# Adafruit_DRV2605L.net
KiCad netlist of a schematic drawn in EAGLE
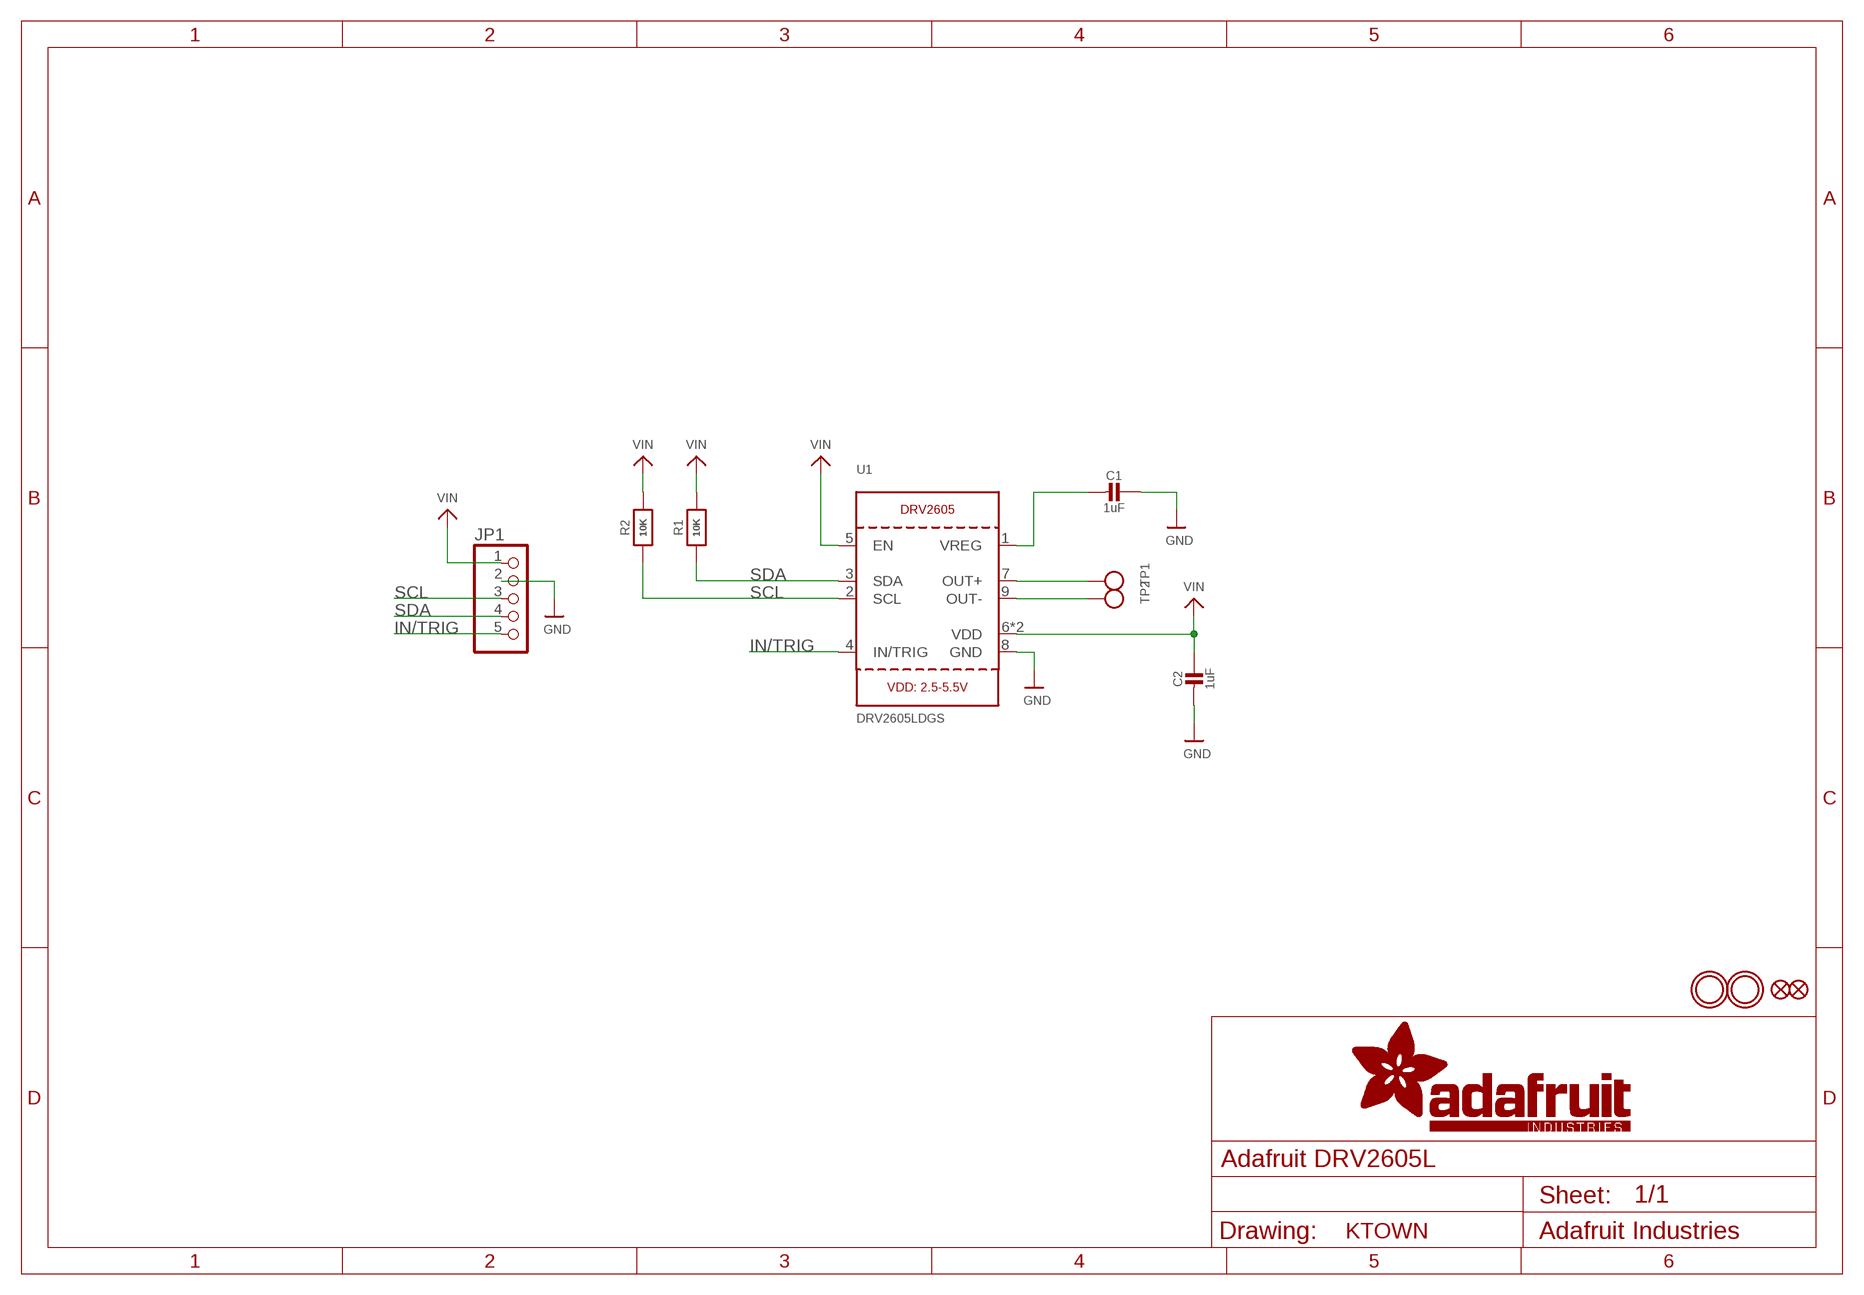
[diagram p0: schematic, sheet 1]

(export (version "E")
  (design (tool "Eeschema 10.0.6"))
  (components
    (comp (ref "C1")
      (value "1uF")
      (footprint "eagle-import:0805-NO")
      (libsource (lib "eagle-import") (part "CAP_CERAMIC0805-NOOUTLINE"))
    )
    (comp (ref "C2")
      (value "1uF")
      (footprint "eagle-import:0805-NO")
      (libsource (lib "eagle-import") (part "CAP_CERAMIC0805-NOOUTLINE"))
    )
    (comp (ref "FID1")
      (value "FIDUCIAL\"\"")
      (footprint "eagle-import:FIDUCIAL_1MM")
      (libsource (lib "eagle-import") (part "FIDUCIAL{dblquote}{dblquote}"))
    )
    (comp (ref "FID2")
      (value "FIDUCIAL\"\"")
      (footprint "eagle-import:FIDUCIAL_1MM")
      (libsource (lib "eagle-import") (part "FIDUCIAL{dblquote}{dblquote}"))
    )
    (comp (ref "JP1")
      (value "HEADER-1X576MIL_FULL")
      (footprint "eagle-import:1X05_ROUND_FULL_76")
      (libsource (lib "eagle-import") (part "HEADER-1X576MIL_FULL"))
    )
    (comp (ref "R1")
      (value "10K")
      (footprint "eagle-import:0805-NO")
      (libsource (lib "eagle-import") (part "RESISTOR0805_NOOUTLINE"))
    )
    (comp (ref "R2")
      (value "10K")
      (footprint "eagle-import:0805-NO")
      (libsource (lib "eagle-import") (part "RESISTOR0805_NOOUTLINE"))
    )
    (comp (ref "TP1")
      (value "TESTPOINTPAD2MM")
      (footprint "eagle-import:TESTPOINT_PAD_2MM")
      (libsource (lib "eagle-import") (part "TESTPOINTPAD2MM"))
    )
    (comp (ref "TP2")
      (value "TESTPOINTPAD2MM")
      (footprint "eagle-import:TESTPOINT_PAD_2MM")
      (libsource (lib "eagle-import") (part "TESTPOINTPAD2MM"))
    )
    (comp (ref "U$2")
      (value "MOUNTINGHOLE2.5")
      (footprint "eagle-import:MOUNTINGHOLE_2.5_PLATED")
      (libsource (lib "eagle-import") (part "MOUNTINGHOLE2.5"))
    )
    (comp (ref "U$3")
      (value "MOUNTINGHOLE2.5")
      (footprint "eagle-import:MOUNTINGHOLE_2.5_PLATED")
      (libsource (lib "eagle-import") (part "MOUNTINGHOLE2.5"))
    )
    (comp (ref "U1")
      (value "DRV2605LDGS")
      (footprint "eagle-import:PSOP10")
      (libsource (lib "eagle-import") (part "DRV2605_SOP"))
    )
  )
  (nets
    (net (code "1") (name "/IN{slash}TRIG") (class "Default")
      (node (ref "JP1") (pin "5") (pinfunction "5_5") (pintype "passive"))
      (node (ref "U1") (pin "4") (pinfunction "IN/TRIG_4") (pintype "input"))
    )
    (net (code "2") (name "/SCL") (class "Default")
      (node (ref "JP1") (pin "3") (pinfunction "3_3") (pintype "passive"))
      (node (ref "R2") (pin "1") (pinfunction "1_1") (pintype "passive"))
      (node (ref "U1") (pin "2") (pinfunction "SCL_2") (pintype "input"))
    )
    (net (code "3") (name "/SDA") (class "Default")
      (node (ref "JP1") (pin "4") (pinfunction "4_4") (pintype "passive"))
      (node (ref "R1") (pin "1") (pinfunction "1_1") (pintype "passive"))
      (node (ref "U1") (pin "3") (pinfunction "SDA_3") (pintype "bidirectional"))
    )
    (net (code "4") (name "GND") (class "Default")
      (node (ref "C1") (pin "1") (pinfunction "1_1") (pintype "passive"))
      (node (ref "C2") (pin "2") (pinfunction "2_2") (pintype "passive"))
      (node (ref "JP1") (pin "2") (pinfunction "2_2") (pintype "passive"))
      (node (ref "U1") (pin "8") (pinfunction "GND_8") (pintype "power_in"))
    )
    (net (code "5") (name "Net-(U1-OUT+)") (class "Default")
      (node (ref "TP1") (pin "P$1") (pinfunction "P$1_P$1") (pintype "bidirectional"))
      (node (ref "U1") (pin "7") (pinfunction "OUT+_7") (pintype "output"))
    )
    (net (code "6") (name "Net-(U1-OUT-)") (class "Default")
      (node (ref "TP2") (pin "P$1") (pinfunction "P$1_P$1") (pintype "bidirectional"))
      (node (ref "U1") (pin "9") (pinfunction "OUT-_9") (pintype "output"))
    )
    (net (code "7") (name "Net-(U1-VREG)") (class "Default")
      (node (ref "C1") (pin "2") (pinfunction "2_2") (pintype "passive"))
      (node (ref "U1") (pin "1") (pinfunction "VREG_1") (pintype "output"))
    )
    (net (code "8") (name "VIN") (class "Default")
      (node (ref "C2") (pin "1") (pinfunction "1_1") (pintype "passive"))
      (node (ref "JP1") (pin "1") (pinfunction "1_1") (pintype "passive"))
      (node (ref "R1") (pin "2") (pinfunction "2_2") (pintype "passive"))
      (node (ref "R2") (pin "2") (pinfunction "2_2") (pintype "passive"))
      (node (ref "U1") (pin "10") (pinfunction "VDD_10") (pintype "power_in"))
      (node (ref "U1") (pin "5") (pinfunction "EN_5") (pintype "input"))
      (node (ref "U1") (pin "6") (pinfunction "VDD_6") (pintype "power_in"))
    )
  )
)
